# SPI_8_bit_display.net
KiCad netlist of a schematic drawn in Altium Designer
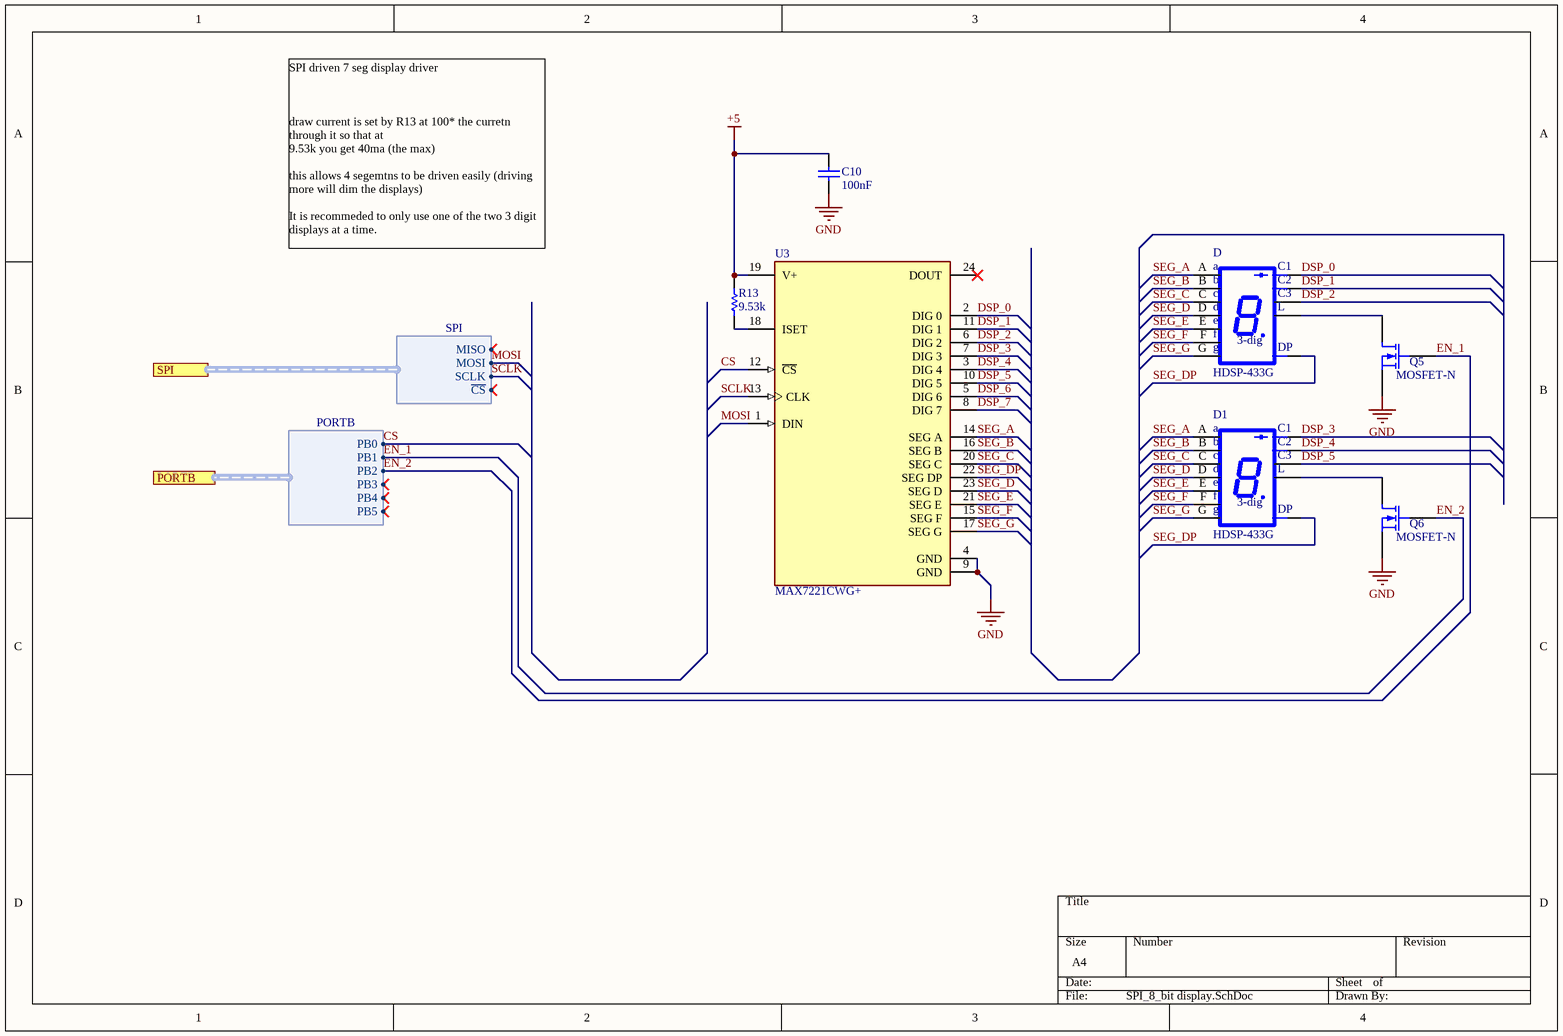
[diagram p0: SPI_8_bit display.SchDoc]

(export (version "E")
  (design (tool "Eeschema 10.0.6"))
  (components
    (comp (ref "C10")
      (value "100nF")
      (description "Capacitor")
      (fields (field (name "PUBLISHER") "Altium Limited"))
      (libsource (lib "Other") (part "100nF"))
    )
    (comp (ref "D")
      (value "HDSP-433G")
      (footprint "SnapEDApcb:HDSP-433G")
      (fields (field (name "MF") "Broadcom Limited") (field (name "DIGI-KEY_PART_NUMBER") "516-3125-ND"))
      (libsource (lib "SnapEDAsch") (part "HDSP-433G"))
    )
    (comp (ref "D1")
      (value "HDSP-433G")
      (footprint "SnapEDApcb:HDSP-433G")
      (fields (field (name "MF") "Broadcom Limited") (field (name "DIGI-KEY_PART_NUMBER") "516-3125-ND"))
      (libsource (lib "SnapEDAsch") (part "HDSP-433G"))
    )
    (comp (ref "Q5")
      (value "MOSFET-N")
      (description "N-Channel MOSFET\r\n2N7002,215 (SOT23) package")
      (fields (field (name "PUBLISHER") "Altium Limited"))
      (libsource (lib "Other") (part "2N7002"))
    )
    (comp (ref "Q6")
      (value "MOSFET-N")
      (description "N-Channel MOSFET\r\n2N7002,215 (SOT23) package")
      (fields (field (name "PUBLISHER") "Altium Limited"))
      (libsource (lib "Other") (part "2N7002"))
    )
    (comp (ref "R13")
      (value "9.53k")
      (description "Resistor")
      (fields (field (name "PUBLISHER") "Altium Limited"))
      (libsource (lib "Other") (part "9.53k"))
    )
    (comp (ref "U3")
      (value "MAX7221CWG+")
      (footprint "FP-W24-1-MFG")
      (description "IC DRVR 7 SEGMNT 8 DIGIT 24SOIC")
      (fields
        (field (name "MANUFACTURER") "Maxim Integrated")
        (field (name "OCTOPART") "https://octopart.com/max7221cwg%2B-maxim+integrated-39581478")
      )
      (libsource (lib "Altium Content Vault") (part "a71a82daf51cffeecc638e415d68d56"))
    )
  )
  (nets
    (net (code "3") (name "+5") (class "Default")
      (node (ref "C10") (pin "2") (pinfunction "2_2") (pintype "passive"))
      (node (ref "R13") (pin "2") (pinfunction "2_2") (pintype "passive"))
      (node (ref "U3") (pin "19") (pinfunction "V+_19") (pintype "power_in"))
    )
    (net (code "4") (name "/CS") (class "Default")
      (node (ref "U3") (pin "12") (pinfunction "~{CS}_12") (pintype "input"))
    )
    (net (code "5") (name "/DSP_0") (class "Default")
      (node (ref "D") (pin "D1") (pinfunction "C1_D1") (pintype "passive"))
      (node (ref "U3") (pin "2") (pinfunction "DIG_0_2") (pintype "passive"))
    )
    (net (code "6") (name "/DSP_1") (class "Default")
      (node (ref "D") (pin "D2") (pinfunction "C2_D2") (pintype "passive"))
      (node (ref "U3") (pin "11") (pinfunction "DIG_1_11") (pintype "passive"))
    )
    (net (code "7") (name "/DSP_2") (class "Default")
      (node (ref "D") (pin "D3") (pinfunction "C3_D3") (pintype "passive"))
      (node (ref "U3") (pin "6") (pinfunction "DIG_2_6") (pintype "passive"))
    )
    (net (code "8") (name "/DSP_3") (class "Default")
      (node (ref "D1") (pin "D1") (pinfunction "C1_D1") (pintype "passive"))
      (node (ref "U3") (pin "7") (pinfunction "DIG_3_7") (pintype "passive"))
    )
    (net (code "9") (name "/DSP_4") (class "Default")
      (node (ref "D1") (pin "D2") (pinfunction "C2_D2") (pintype "passive"))
      (node (ref "U3") (pin "3") (pinfunction "DIG_4_3") (pintype "passive"))
    )
    (net (code "10") (name "/DSP_5") (class "Default")
      (node (ref "D1") (pin "D3") (pinfunction "C3_D3") (pintype "passive"))
      (node (ref "U3") (pin "10") (pinfunction "DIG_5_10") (pintype "passive"))
    )
    (net (code "11") (name "/DSP_6") (class "Default")
      (node (ref "U3") (pin "5") (pinfunction "DIG_6_5") (pintype "passive"))
    )
    (net (code "12") (name "/DSP_7") (class "Default")
      (node (ref "U3") (pin "8") (pinfunction "DIG_7_8") (pintype "passive"))
    )
    (net (code "13") (name "/EN_1") (class "Default")
      (node (ref "Q5") (pin "2") (pinfunction "G_2") (pintype "passive"))
      (node (ref "Q6") (pin "2") (pinfunction "G_2") (pintype "passive"))
    )
    (net (code "14") (name "/MOSI") (class "Default")
      (node (ref "U3") (pin "1") (pinfunction "DIN_1") (pintype "input"))
    )
    (net (code "15") (name "/SCLK") (class "Default")
      (node (ref "U3") (pin "13") (pinfunction "CLK_13") (pintype "input"))
    )
    (net (code "16") (name "/SEG_A") (class "Default")
      (node (ref "D") (pin "A") (pinfunction "A_A") (pintype "passive"))
      (node (ref "D1") (pin "A") (pinfunction "A_A") (pintype "passive"))
      (node (ref "U3") (pin "14") (pinfunction "SEG_A_14") (pintype "passive"))
    )
    (net (code "17") (name "/SEG_B") (class "Default")
      (node (ref "D") (pin "B") (pinfunction "B_B") (pintype "passive"))
      (node (ref "D1") (pin "B") (pinfunction "B_B") (pintype "passive"))
      (node (ref "U3") (pin "16") (pinfunction "SEG_B_16") (pintype "passive"))
    )
    (net (code "18") (name "/SEG_C") (class "Default")
      (node (ref "D") (pin "C") (pinfunction "C_C") (pintype "passive"))
      (node (ref "D1") (pin "C") (pinfunction "C_C") (pintype "passive"))
      (node (ref "U3") (pin "20") (pinfunction "SEG_C_20") (pintype "passive"))
    )
    (net (code "19") (name "/SEG_D") (class "Default")
      (node (ref "D") (pin "D") (pinfunction "D_D") (pintype "passive"))
      (node (ref "D1") (pin "D") (pinfunction "D_D") (pintype "passive"))
      (node (ref "U3") (pin "23") (pinfunction "SEG_D_23") (pintype "passive"))
    )
    (net (code "20") (name "/SEG_DP") (class "Default")
      (node (ref "D") (pin "DP") (pinfunction "DP_DP") (pintype "passive"))
      (node (ref "D1") (pin "DP") (pinfunction "DP_DP") (pintype "passive"))
      (node (ref "U3") (pin "22") (pinfunction "SEG_DP_22") (pintype "passive"))
    )
    (net (code "21") (name "/SEG_E") (class "Default")
      (node (ref "D") (pin "E") (pinfunction "E_E") (pintype "passive"))
      (node (ref "D1") (pin "E") (pinfunction "E_E") (pintype "passive"))
      (node (ref "U3") (pin "21") (pinfunction "SEG_E_21") (pintype "passive"))
    )
    (net (code "22") (name "/SEG_F") (class "Default")
      (node (ref "D") (pin "F") (pinfunction "F_F") (pintype "passive"))
      (node (ref "D1") (pin "F") (pinfunction "F_F") (pintype "passive"))
      (node (ref "U3") (pin "15") (pinfunction "SEG_F_15") (pintype "passive"))
    )
    (net (code "23") (name "/SEG_G") (class "Default")
      (node (ref "D") (pin "G") (pinfunction "G_G") (pintype "passive"))
      (node (ref "D1") (pin "G") (pinfunction "G_G") (pintype "passive"))
      (node (ref "U3") (pin "17") (pinfunction "SEG_G_17") (pintype "passive"))
    )
    (net (code "26") (name "GND") (class "Default")
      (node (ref "C10") (pin "1") (pinfunction "1_1") (pintype "passive"))
      (node (ref "Q5") (pin "3") (pinfunction "S_3") (pintype "passive"))
      (node (ref "Q6") (pin "3") (pinfunction "S_3") (pintype "passive"))
      (node (ref "U3") (pin "4") (pinfunction "GND_4") (pintype "power_in"))
      (node (ref "U3") (pin "9") (pinfunction "GND_9") (pintype "power_in"))
    )
    (net (code "27") (name "Net-(D-P$1)") (class "Default")
      (node (ref "D") (pin "L") (pinfunction "P$1_L") (pintype "passive"))
      (node (ref "Q5") (pin "1") (pinfunction "D_1") (pintype "passive"))
    )
    (net (code "28") (name "Net-(D1-P$1)") (class "Default")
      (node (ref "D1") (pin "L") (pinfunction "P$1_L") (pintype "passive"))
      (node (ref "Q6") (pin "1") (pinfunction "D_1") (pintype "passive"))
    )
    (net (code "29") (name "Net-(U3-ISET)") (class "Default")
      (node (ref "R13") (pin "1") (pinfunction "1_1") (pintype "passive"))
      (node (ref "U3") (pin "18") (pinfunction "ISET_18") (pintype "passive"))
    )
    (net (code "30") (name "unconnected-(U3-DOUT-Pad24)") (class "Default")
      (node (ref "U3") (pin "24") (pinfunction "DOUT_24") (pintype "passive+no_connect"))
    )
  )
)
